# Sheet1.net
KiCad netlist of a schematic drawn in Altium Designer
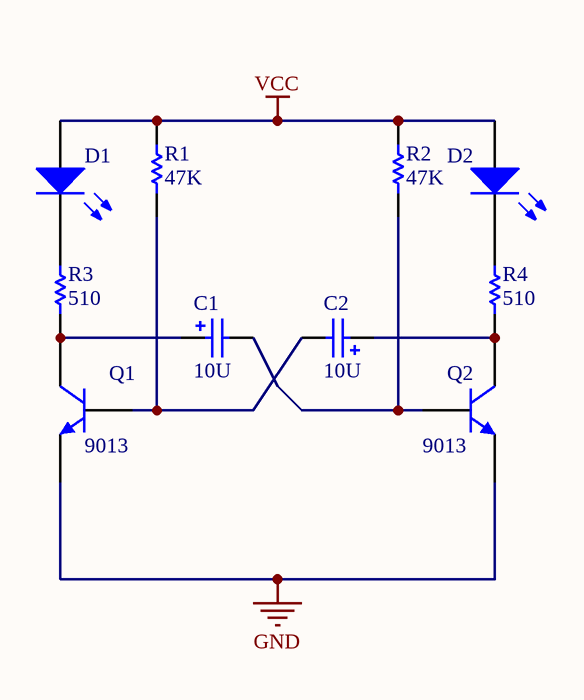
[diagram p0: Sheet1.SchDoc]

(export (version "E")
  (design (tool "Eeschema 10.0.6"))
  (components
    (comp (ref "C1")
      (value "10U")
      (footprint "CAPPR2-5x6.8")
      (description "Polarized Capacitor (Axial)")
      (fields (field (name "PUBLISHER") "Altium Limited"))
      (libsource (lib "Miscellaneous Devices") (part "Cap Pol2"))
    )
    (comp (ref "C2")
      (value "10U")
      (footprint "CAPPR2-5x6.8")
      (description "Polarized Capacitor (Axial)")
      (fields (field (name "PUBLISHER") "Altium Limited"))
      (libsource (lib "Miscellaneous Devices") (part "Cap Pol2"))
    )
    (comp (ref "D1")
      (value "~")
      (footprint "CAPPR2-5x6.8")
      (description "Typical INFRARED GaAs LED")
      (fields (field (name "PUBLISHER") "Altium Limited"))
      (libsource (lib "Miscellaneous Devices") (part "LED0"))
    )
    (comp (ref "D2")
      (value "~")
      (footprint "CAPPR2-5x6.8")
      (description "Typical INFRARED GaAs LED")
      (fields (field (name "PUBLISHER") "Altium Limited"))
      (libsource (lib "Miscellaneous Devices") (part "LED0"))
    )
    (comp (ref "Q1")
      (value "9013")
      (footprint "BCY-W3/E4")
      (description "NPN General Purpose Amplifier")
      (fields (field (name "PUBLISHER") "Altium Limited"))
      (libsource (lib "Miscellaneous Devices") (part "2N3904"))
    )
    (comp (ref "Q2")
      (value "9013")
      (footprint "BCY-W3/E4")
      (description "NPN General Purpose Amplifier")
      (fields (field (name "PUBLISHER") "Altium Limited"))
      (libsource (lib "Miscellaneous Devices") (part "2N3904"))
    )
    (comp (ref "R1")
      (value "47K")
      (footprint "AXIAL-0.3")
      (description "Resistor")
      (fields (field (name "PUBLISHER") "Altium Limited"))
      (libsource (lib "Miscellaneous Devices") (part "Res1"))
    )
    (comp (ref "R2")
      (value "47K")
      (footprint "AXIAL-0.3")
      (description "Resistor")
      (fields (field (name "PUBLISHER") "Altium Limited"))
      (libsource (lib "Miscellaneous Devices") (part "Res1"))
    )
    (comp (ref "R3")
      (value "510")
      (footprint "AXIAL-0.3")
      (description "Resistor")
      (fields (field (name "PUBLISHER") "Altium Limited"))
      (libsource (lib "Miscellaneous Devices") (part "Res1"))
    )
    (comp (ref "R4")
      (value "510")
      (footprint "AXIAL-0.3")
      (description "Resistor")
      (fields (field (name "PUBLISHER") "Altium Limited"))
      (libsource (lib "Miscellaneous Devices") (part "Res1"))
    )
  )
  (nets
    (net (code "1") (name "GND") (class "Default")
      (node (ref "Q1") (pin "1") (pinfunction "E_1") (pintype "passive"))
      (node (ref "Q2") (pin "1") (pinfunction "E_1") (pintype "passive"))
    )
    (net (code "2") (name "Net-(D1-K)") (class "Default")
      (node (ref "D1") (pin "2") (pinfunction "K_2") (pintype "passive"))
      (node (ref "R3") (pin "2") (pinfunction "2_2") (pintype "passive"))
    )
    (net (code "3") (name "Net-(D2-K)") (class "Default")
      (node (ref "D2") (pin "2") (pinfunction "K_2") (pintype "passive"))
      (node (ref "R4") (pin "2") (pinfunction "2_2") (pintype "passive"))
    )
    (net (code "4") (name "Net-(Q1-B)") (class "Default")
      (node (ref "C2") (pin "2") (pinfunction "2_2") (pintype "passive"))
      (node (ref "Q1") (pin "2") (pinfunction "B_2") (pintype "passive"))
      (node (ref "R1") (pin "1") (pinfunction "1_1") (pintype "passive"))
    )
    (net (code "5") (name "Net-(Q1-C)") (class "Default")
      (node (ref "C1") (pin "1") (pinfunction "1_1") (pintype "passive"))
      (node (ref "Q1") (pin "3") (pinfunction "C_3") (pintype "passive"))
      (node (ref "R3") (pin "1") (pinfunction "1_1") (pintype "passive"))
    )
    (net (code "6") (name "Net-(Q2-B)") (class "Default")
      (node (ref "C1") (pin "2") (pinfunction "2_2") (pintype "passive"))
      (node (ref "Q2") (pin "2") (pinfunction "B_2") (pintype "passive"))
      (node (ref "R2") (pin "1") (pinfunction "1_1") (pintype "passive"))
    )
    (net (code "7") (name "Net-(Q2-C)") (class "Default")
      (node (ref "C2") (pin "1") (pinfunction "1_1") (pintype "passive"))
      (node (ref "Q2") (pin "3") (pinfunction "C_3") (pintype "passive"))
      (node (ref "R4") (pin "1") (pinfunction "1_1") (pintype "passive"))
    )
    (net (code "8") (name "VCC") (class "Default")
      (node (ref "D1") (pin "1") (pinfunction "A_1") (pintype "passive"))
      (node (ref "D2") (pin "1") (pinfunction "A_1") (pintype "passive"))
      (node (ref "R1") (pin "2") (pinfunction "2_2") (pintype "passive"))
      (node (ref "R2") (pin "2") (pinfunction "2_2") (pintype "passive"))
    )
  )
)
